# AUDIO_SHIELD.net
KiCad netlist of a schematic drawn in EAGLE
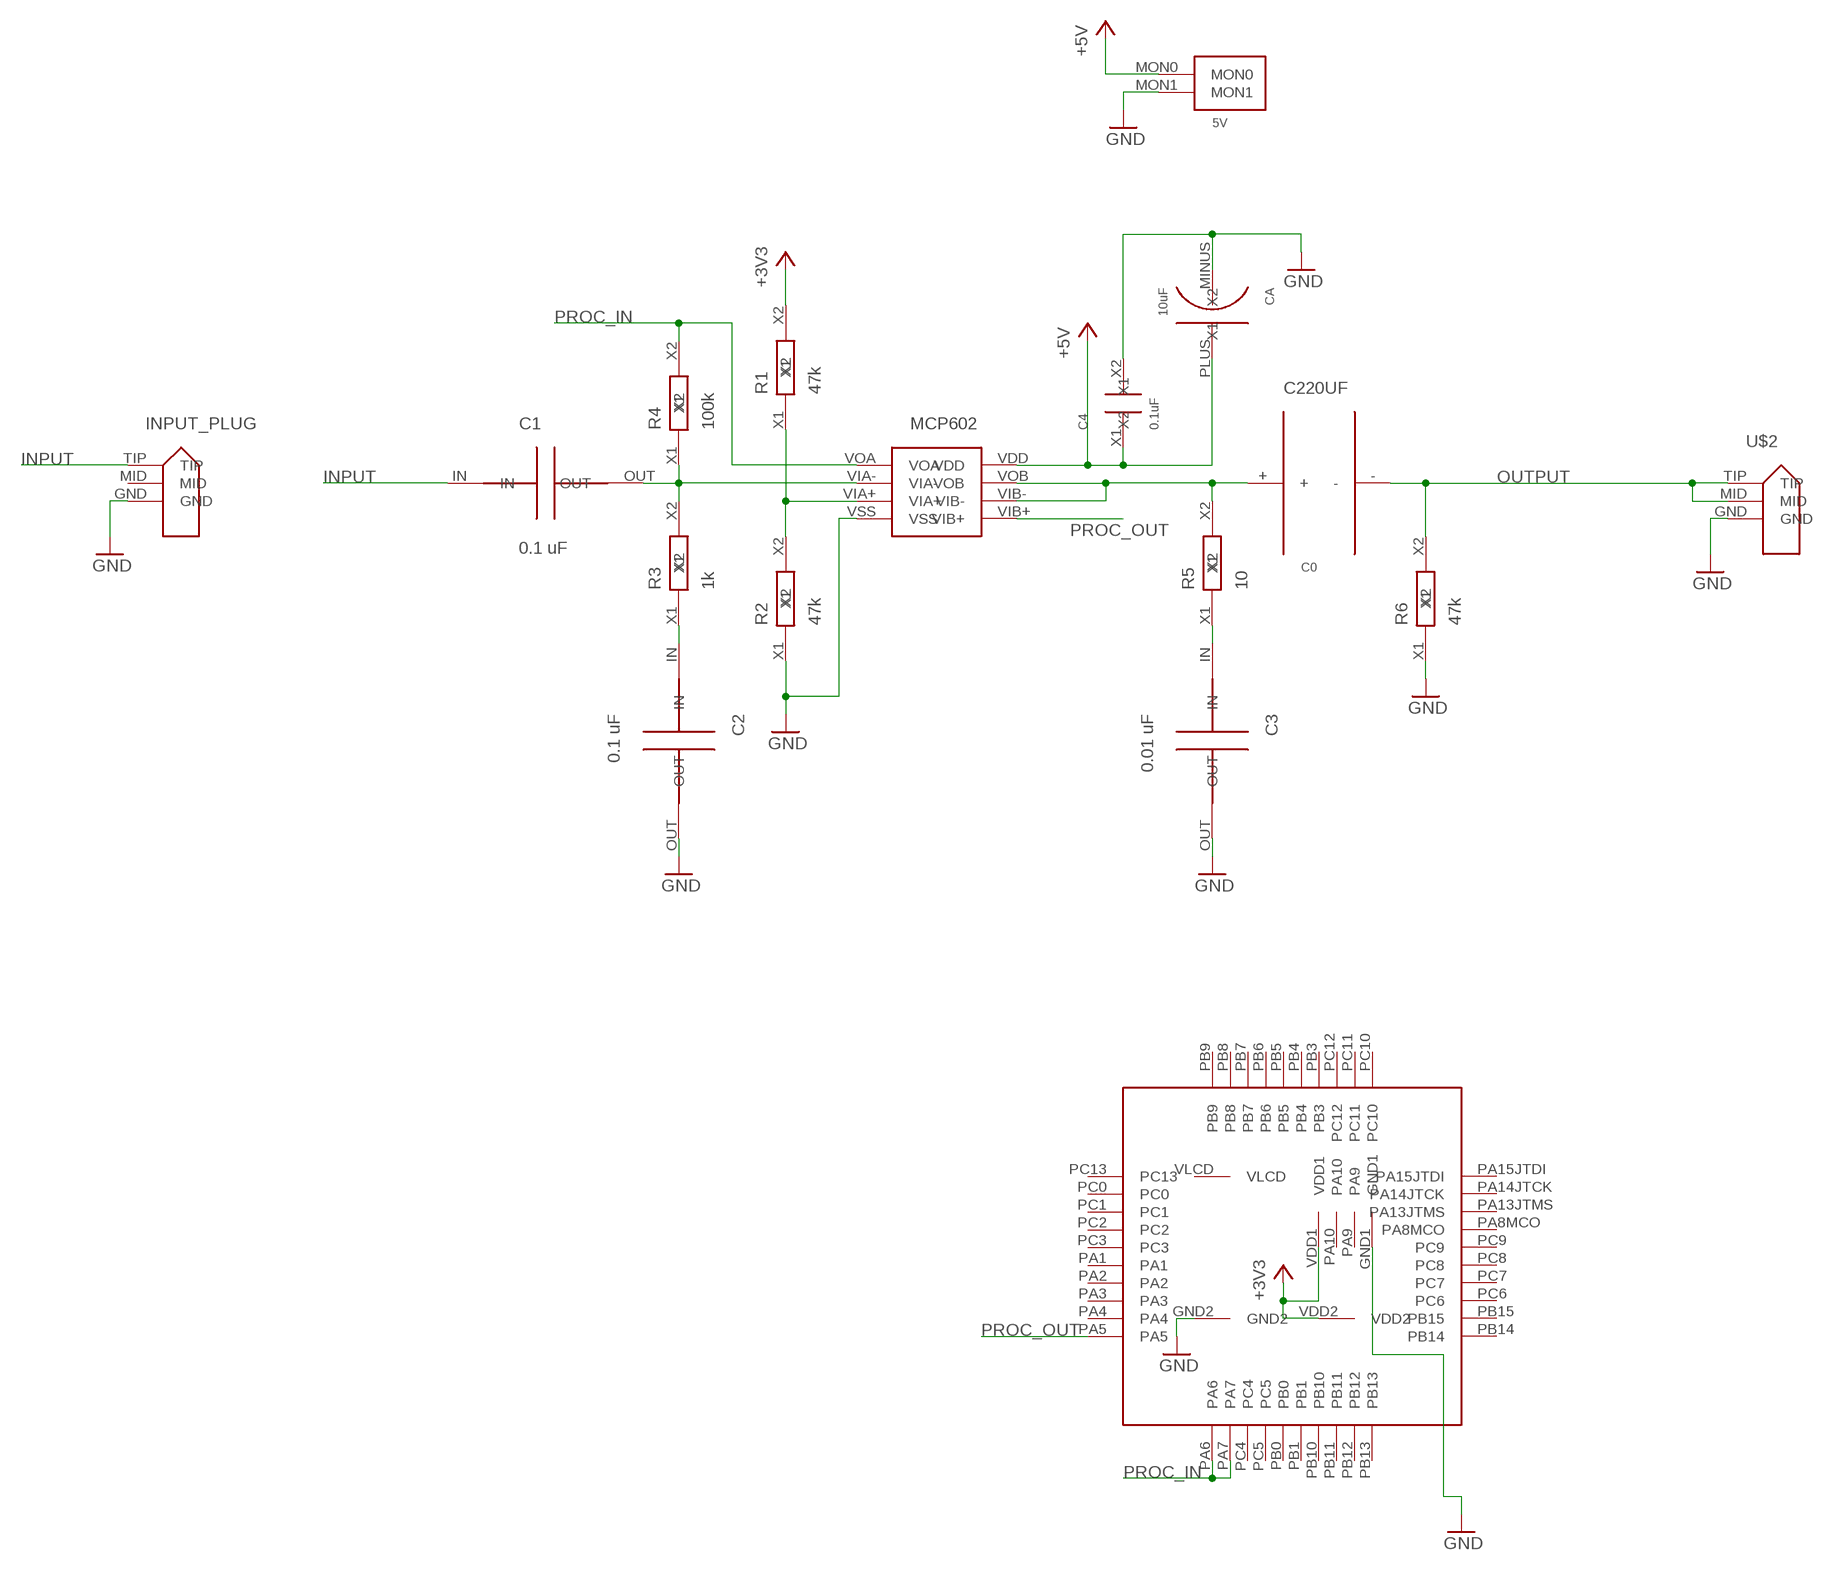
[diagram p0: schematic, sheet 1]

(export (version "E")
  (design (tool "Eeschema 10.0.6"))
  (components
    (comp (ref "5V")
      (value "MON2PIN")
      (footprint "eagle-import:MON2PIN")
      (libsource (lib "eagle-import") (part "MON2PIN"))
    )
    (comp (ref "C0")
      (value "C220UF")
      (footprint "eagle-import:C100UF")
      (libsource (lib "eagle-import") (part "C100UF"))
    )
    (comp (ref "C1")
      (value "0.1 uF")
      (footprint "eagle-import:C_CER_5MM")
      (libsource (lib "eagle-import") (part "C_CER_5MM"))
    )
    (comp (ref "C2")
      (value "0.1 uF")
      (footprint "eagle-import:C_CER_5MM")
      (libsource (lib "eagle-import") (part "C_CER_5MM"))
    )
    (comp (ref "C3")
      (value "0.01 uF")
      (footprint "eagle-import:C_CER_5MM")
      (libsource (lib "eagle-import") (part "C_CER_5MM"))
    )
    (comp (ref "C4")
      (value "0.1uF")
      (footprint "eagle-import:SMD_2.1X1.25")
      (libsource (lib "eagle-import") (part "C_SMD_2.1X1.25"))
    )
    (comp (ref "CA")
      (value "10uF")
      (footprint "eagle-import:C_SMD_TA_A")
      (libsource (lib "eagle-import") (part "C_SMD_TA_A"))
    )
    (comp (ref "INPUT_PLUG")
      (value "AUDIOJACK_ST215N")
      (footprint "eagle-import:AUDIOJACK_ST215N")
      (libsource (lib "eagle-import") (part "AUDIOJACK_ST215N"))
    )
    (comp (ref "MCP602")
      (value "MCP602")
      (footprint "eagle-import:MCP602")
      (libsource (lib "eagle-import") (part "MCP602"))
    )
    (comp (ref "R1")
      (value "47k")
      (footprint "eagle-import:SMD_2.1X1.25")
      (libsource (lib "eagle-import") (part "R_SMD_2.1X1.25"))
    )
    (comp (ref "R2")
      (value "47k")
      (footprint "eagle-import:SMD_2.1X1.25")
      (libsource (lib "eagle-import") (part "R_SMD_2.1X1.25"))
    )
    (comp (ref "R3")
      (value "1k")
      (footprint "eagle-import:SMD_2.1X1.25")
      (libsource (lib "eagle-import") (part "R_SMD_2.1X1.25"))
    )
    (comp (ref "R4")
      (value "100k")
      (footprint "eagle-import:SMD_2.1X1.25")
      (libsource (lib "eagle-import") (part "R_SMD_2.1X1.25"))
    )
    (comp (ref "R5")
      (value "10")
      (footprint "eagle-import:SMD_2.1X1.25")
      (libsource (lib "eagle-import") (part "R_SMD_2.1X1.25"))
    )
    (comp (ref "R6")
      (value "47k")
      (footprint "eagle-import:SMD_2.1X1.25")
      (libsource (lib "eagle-import") (part "R_SMD_2.1X1.25"))
    )
    (comp (ref "U$1")
      (value "STM32L1_ADAPTER")
      (footprint "eagle-import:STM32L1_ADAPTER")
      (libsource (lib "eagle-import") (part "STM32L1_ADAPTER"))
    )
    (comp (ref "U$2")
      (value "AUDIOJACK_ST215N")
      (footprint "eagle-import:AUDIOJACK_ST215N")
      (libsource (lib "eagle-import") (part "AUDIOJACK_ST215N"))
    )
  )
  (nets
    (net (code "1") (name "+3V3") (class "Default")
      (node (ref "R1") (pin "X2") (pinfunction "X2_X2") (pintype "bidirectional"))
      (node (ref "U$1") (pin "VDD1") (pinfunction "VDD1_VDD1") (pintype "bidirectional"))
      (node (ref "U$1") (pin "VDD2") (pinfunction "VDD2_VDD2") (pintype "bidirectional"))
    )
    (net (code "2") (name "+5V") (class "Default")
      (node (ref "5V") (pin "MON0") (pinfunction "MON0_MON0") (pintype "bidirectional"))
      (node (ref "C4") (pin "X1") (pinfunction "X1_X1") (pintype "bidirectional"))
      (node (ref "CA") (pin "PLUS") (pinfunction "X2_PLUS") (pintype "bidirectional"))
      (node (ref "MCP602") (pin "VDD") (pinfunction "VDD_VDD") (pintype "bidirectional"))
    )
    (net (code "3") (name "/INPUT") (class "Default")
      (node (ref "C1") (pin "IN") (pinfunction "IN_IN") (pintype "bidirectional"))
      (node (ref "INPUT_PLUG") (pin "TIP") (pinfunction "TIP_TIP") (pintype "bidirectional"))
    )
    (net (code "4") (name "/OUTPUT") (class "Default")
      (node (ref "C0") (pin "-") (pinfunction "-_-") (pintype "bidirectional"))
      (node (ref "R6") (pin "X2") (pinfunction "X2_X2") (pintype "bidirectional"))
      (node (ref "U$2") (pin "MID") (pinfunction "MID_MID") (pintype "bidirectional"))
      (node (ref "U$2") (pin "TIP") (pinfunction "TIP_TIP") (pintype "bidirectional"))
    )
    (net (code "5") (name "/PROC_IN") (class "Default")
      (node (ref "MCP602") (pin "VOA") (pinfunction "VOA_VOA") (pintype "bidirectional"))
      (node (ref "R4") (pin "X2") (pinfunction "X2_X2") (pintype "bidirectional"))
      (node (ref "U$1") (pin "PA6") (pinfunction "PA6_PA6") (pintype "bidirectional"))
      (node (ref "U$1") (pin "PA7") (pinfunction "PA7_PA7") (pintype "bidirectional"))
    )
    (net (code "6") (name "/PROC_OUT") (class "Default")
      (node (ref "MCP602") (pin "VIB+") (pinfunction "VIB+_VIB+") (pintype "bidirectional"))
      (node (ref "U$1") (pin "PA5") (pinfunction "PA5_PA5") (pintype "bidirectional"))
    )
    (net (code "7") (name "GND") (class "Default")
      (node (ref "5V") (pin "MON1") (pinfunction "MON1_MON1") (pintype "bidirectional"))
      (node (ref "C2") (pin "OUT") (pinfunction "OUT_OUT") (pintype "bidirectional"))
      (node (ref "C3") (pin "OUT") (pinfunction "OUT_OUT") (pintype "bidirectional"))
      (node (ref "C4") (pin "X2") (pinfunction "X2_X2") (pintype "bidirectional"))
      (node (ref "CA") (pin "MINUS") (pinfunction "X1_MINUS") (pintype "bidirectional"))
      (node (ref "INPUT_PLUG") (pin "GND") (pinfunction "GND_GND") (pintype "bidirectional"))
      (node (ref "MCP602") (pin "VSS") (pinfunction "VSS_VSS") (pintype "bidirectional"))
      (node (ref "R2") (pin "X1") (pinfunction "X1_X1") (pintype "bidirectional"))
      (node (ref "R6") (pin "X1") (pinfunction "X1_X1") (pintype "bidirectional"))
      (node (ref "U$1") (pin "GND1") (pinfunction "GND1_GND1") (pintype "bidirectional"))
      (node (ref "U$1") (pin "GND2") (pinfunction "GND2_GND2") (pintype "bidirectional"))
      (node (ref "U$2") (pin "GND") (pinfunction "GND_GND") (pintype "bidirectional"))
    )
    (net (code "8") (name "Net-(C0-Pad+)") (class "Default")
      (node (ref "C0") (pin "+") (pinfunction "+_+") (pintype "bidirectional"))
      (node (ref "MCP602") (pin "VIB-") (pinfunction "VIB-_VIB-") (pintype "bidirectional"))
      (node (ref "MCP602") (pin "VOB") (pinfunction "VOB_VOB") (pintype "bidirectional"))
      (node (ref "R5") (pin "X2") (pinfunction "X2_X2") (pintype "bidirectional"))
    )
    (net (code "9") (name "Net-(C1-PadOUT)") (class "Default")
      (node (ref "C1") (pin "OUT") (pinfunction "OUT_OUT") (pintype "bidirectional"))
      (node (ref "MCP602") (pin "VIA-") (pinfunction "VIA-_VIA-") (pintype "bidirectional"))
      (node (ref "R3") (pin "X2") (pinfunction "X2_X2") (pintype "bidirectional"))
      (node (ref "R4") (pin "X1") (pinfunction "X1_X1") (pintype "bidirectional"))
    )
    (net (code "10") (name "Net-(C2-PadIN)") (class "Default")
      (node (ref "C2") (pin "IN") (pinfunction "IN_IN") (pintype "bidirectional"))
      (node (ref "R3") (pin "X1") (pinfunction "X1_X1") (pintype "bidirectional"))
    )
    (net (code "11") (name "Net-(C3-PadIN)") (class "Default")
      (node (ref "C3") (pin "IN") (pinfunction "IN_IN") (pintype "bidirectional"))
      (node (ref "R5") (pin "X1") (pinfunction "X1_X1") (pintype "bidirectional"))
    )
    (net (code "12") (name "Net-(MCP602-PadVIA+)") (class "Default")
      (node (ref "MCP602") (pin "VIA+") (pinfunction "VIA+_VIA+") (pintype "bidirectional"))
      (node (ref "R1") (pin "X1") (pinfunction "X1_X1") (pintype "bidirectional"))
      (node (ref "R2") (pin "X2") (pinfunction "X2_X2") (pintype "bidirectional"))
    )
    (net (code "13") (name "unconnected-(INPUT_PLUG-PadMID)") (class "Default")
      (node (ref "INPUT_PLUG") (pin "MID") (pinfunction "MID_MID") (pintype "bidirectional"))
    )
    (net (code "14") (name "unconnected-(U$1-PadPA1)") (class "Default")
      (node (ref "U$1") (pin "PA1") (pinfunction "PA1_PA1") (pintype "bidirectional"))
    )
    (net (code "15") (name "unconnected-(U$1-PadPA2)") (class "Default")
      (node (ref "U$1") (pin "PA2") (pinfunction "PA2_PA2") (pintype "bidirectional"))
    )
    (net (code "16") (name "unconnected-(U$1-PadPA3)") (class "Default")
      (node (ref "U$1") (pin "PA3") (pinfunction "PA3_PA3") (pintype "bidirectional"))
    )
    (net (code "17") (name "unconnected-(U$1-PadPA4)") (class "Default")
      (node (ref "U$1") (pin "PA4") (pinfunction "PA4_PA4") (pintype "bidirectional"))
    )
    (net (code "18") (name "unconnected-(U$1-PadPA8MCO)") (class "Default")
      (node (ref "U$1") (pin "PA8MCO") (pinfunction "PA8MCO_PA8MCO") (pintype "bidirectional"))
    )
    (net (code "19") (name "unconnected-(U$1-PadPA9)") (class "Default")
      (node (ref "U$1") (pin "PA9") (pinfunction "PA9_PA9") (pintype "bidirectional"))
    )
    (net (code "20") (name "unconnected-(U$1-PadPA10)") (class "Default")
      (node (ref "U$1") (pin "PA10") (pinfunction "PA10_PA10") (pintype "bidirectional"))
    )
    (net (code "21") (name "unconnected-(U$1-PadPA13JTMS)") (class "Default")
      (node (ref "U$1") (pin "PA13JTMS") (pinfunction "PA13JTMS_PA13JTMS") (pintype "bidirectional"))
    )
    (net (code "22") (name "unconnected-(U$1-PadPA14JTCK)") (class "Default")
      (node (ref "U$1") (pin "PA14JTCK") (pinfunction "PA14JTCK_PA14JTCK") (pintype "bidirectional"))
    )
    (net (code "23") (name "unconnected-(U$1-PadPA15JTDI)") (class "Default")
      (node (ref "U$1") (pin "PA15JTDI") (pinfunction "PA15JTDI_PA15JTDI") (pintype "bidirectional"))
    )
    (net (code "24") (name "unconnected-(U$1-PadPB0)") (class "Default")
      (node (ref "U$1") (pin "PB0") (pinfunction "PB0_PB0") (pintype "bidirectional"))
    )
    (net (code "25") (name "unconnected-(U$1-PadPB1)") (class "Default")
      (node (ref "U$1") (pin "PB1") (pinfunction "PB1_PB1") (pintype "bidirectional"))
    )
    (net (code "26") (name "unconnected-(U$1-PadPB3)") (class "Default")
      (node (ref "U$1") (pin "PB3") (pinfunction "PB3_PB3") (pintype "bidirectional"))
    )
    (net (code "27") (name "unconnected-(U$1-PadPB4)") (class "Default")
      (node (ref "U$1") (pin "PB4") (pinfunction "PB4_PB4") (pintype "bidirectional"))
    )
    (net (code "28") (name "unconnected-(U$1-PadPB5)") (class "Default")
      (node (ref "U$1") (pin "PB5") (pinfunction "PB5_PB5") (pintype "bidirectional"))
    )
    (net (code "29") (name "unconnected-(U$1-PadPB6)") (class "Default")
      (node (ref "U$1") (pin "PB6") (pinfunction "PB6_PB6") (pintype "bidirectional"))
    )
    (net (code "30") (name "unconnected-(U$1-PadPB7)") (class "Default")
      (node (ref "U$1") (pin "PB7") (pinfunction "PB7_PB7") (pintype "bidirectional"))
    )
    (net (code "31") (name "unconnected-(U$1-PadPB8)") (class "Default")
      (node (ref "U$1") (pin "PB8") (pinfunction "PB8_PB8") (pintype "bidirectional"))
    )
    (net (code "32") (name "unconnected-(U$1-PadPB9)") (class "Default")
      (node (ref "U$1") (pin "PB9") (pinfunction "PB9_PB9") (pintype "bidirectional"))
    )
    (net (code "33") (name "unconnected-(U$1-PadPB10)") (class "Default")
      (node (ref "U$1") (pin "PB10") (pinfunction "PB10_PB10") (pintype "bidirectional"))
    )
    (net (code "34") (name "unconnected-(U$1-PadPB11)") (class "Default")
      (node (ref "U$1") (pin "PB11") (pinfunction "PB11_PB11") (pintype "bidirectional"))
    )
    (net (code "35") (name "unconnected-(U$1-PadPB12)") (class "Default")
      (node (ref "U$1") (pin "PB12") (pinfunction "PB12_PB12") (pintype "bidirectional"))
    )
    (net (code "36") (name "unconnected-(U$1-PadPB13)") (class "Default")
      (node (ref "U$1") (pin "PB13") (pinfunction "PB13_PB13") (pintype "bidirectional"))
    )
    (net (code "37") (name "unconnected-(U$1-PadPB14)") (class "Default")
      (node (ref "U$1") (pin "PB14") (pinfunction "PB14_PB14") (pintype "bidirectional"))
    )
    (net (code "38") (name "unconnected-(U$1-PadPB15)") (class "Default")
      (node (ref "U$1") (pin "PB15") (pinfunction "PB15_PB15") (pintype "bidirectional"))
    )
    (net (code "39") (name "unconnected-(U$1-PadPC0)") (class "Default")
      (node (ref "U$1") (pin "PC0") (pinfunction "PC0_PC0") (pintype "bidirectional"))
    )
    (net (code "40") (name "unconnected-(U$1-PadPC1)") (class "Default")
      (node (ref "U$1") (pin "PC1") (pinfunction "PC1_PC1") (pintype "bidirectional"))
    )
    (net (code "41") (name "unconnected-(U$1-PadPC2)") (class "Default")
      (node (ref "U$1") (pin "PC2") (pinfunction "PC2_PC2") (pintype "bidirectional"))
    )
    (net (code "42") (name "unconnected-(U$1-PadPC3)") (class "Default")
      (node (ref "U$1") (pin "PC3") (pinfunction "PC3_PC3") (pintype "bidirectional"))
    )
    (net (code "43") (name "unconnected-(U$1-PadPC4)") (class "Default")
      (node (ref "U$1") (pin "PC4") (pinfunction "PC4_PC4") (pintype "bidirectional"))
    )
    (net (code "44") (name "unconnected-(U$1-PadPC5)") (class "Default")
      (node (ref "U$1") (pin "PC5") (pinfunction "PC5_PC5") (pintype "bidirectional"))
    )
    (net (code "45") (name "unconnected-(U$1-PadPC6)") (class "Default")
      (node (ref "U$1") (pin "PC6") (pinfunction "PC6_PC6") (pintype "bidirectional"))
    )
    (net (code "46") (name "unconnected-(U$1-PadPC7)") (class "Default")
      (node (ref "U$1") (pin "PC7") (pinfunction "PC7_PC7") (pintype "bidirectional"))
    )
    (net (code "47") (name "unconnected-(U$1-PadPC8)") (class "Default")
      (node (ref "U$1") (pin "PC8") (pinfunction "PC8_PC8") (pintype "bidirectional"))
    )
    (net (code "48") (name "unconnected-(U$1-PadPC9)") (class "Default")
      (node (ref "U$1") (pin "PC9") (pinfunction "PC9_PC9") (pintype "bidirectional"))
    )
    (net (code "49") (name "unconnected-(U$1-PadPC10)") (class "Default")
      (node (ref "U$1") (pin "PC10") (pinfunction "PC10_PC10") (pintype "bidirectional"))
    )
    (net (code "50") (name "unconnected-(U$1-PadPC11)") (class "Default")
      (node (ref "U$1") (pin "PC11") (pinfunction "PC11_PC11") (pintype "bidirectional"))
    )
    (net (code "51") (name "unconnected-(U$1-PadPC12)") (class "Default")
      (node (ref "U$1") (pin "PC12") (pinfunction "PC12_PC12") (pintype "bidirectional"))
    )
    (net (code "52") (name "unconnected-(U$1-PadPC13)") (class "Default")
      (node (ref "U$1") (pin "PC13") (pinfunction "PC13_PC13") (pintype "bidirectional"))
    )
    (net (code "53") (name "unconnected-(U$1-PadVLCD)") (class "Default")
      (node (ref "U$1") (pin "VLCD") (pinfunction "VLCD_VLCD") (pintype "bidirectional"))
    )
  )
)
